# HDMI.net
KiCad netlist of a schematic drawn in Altium Designer
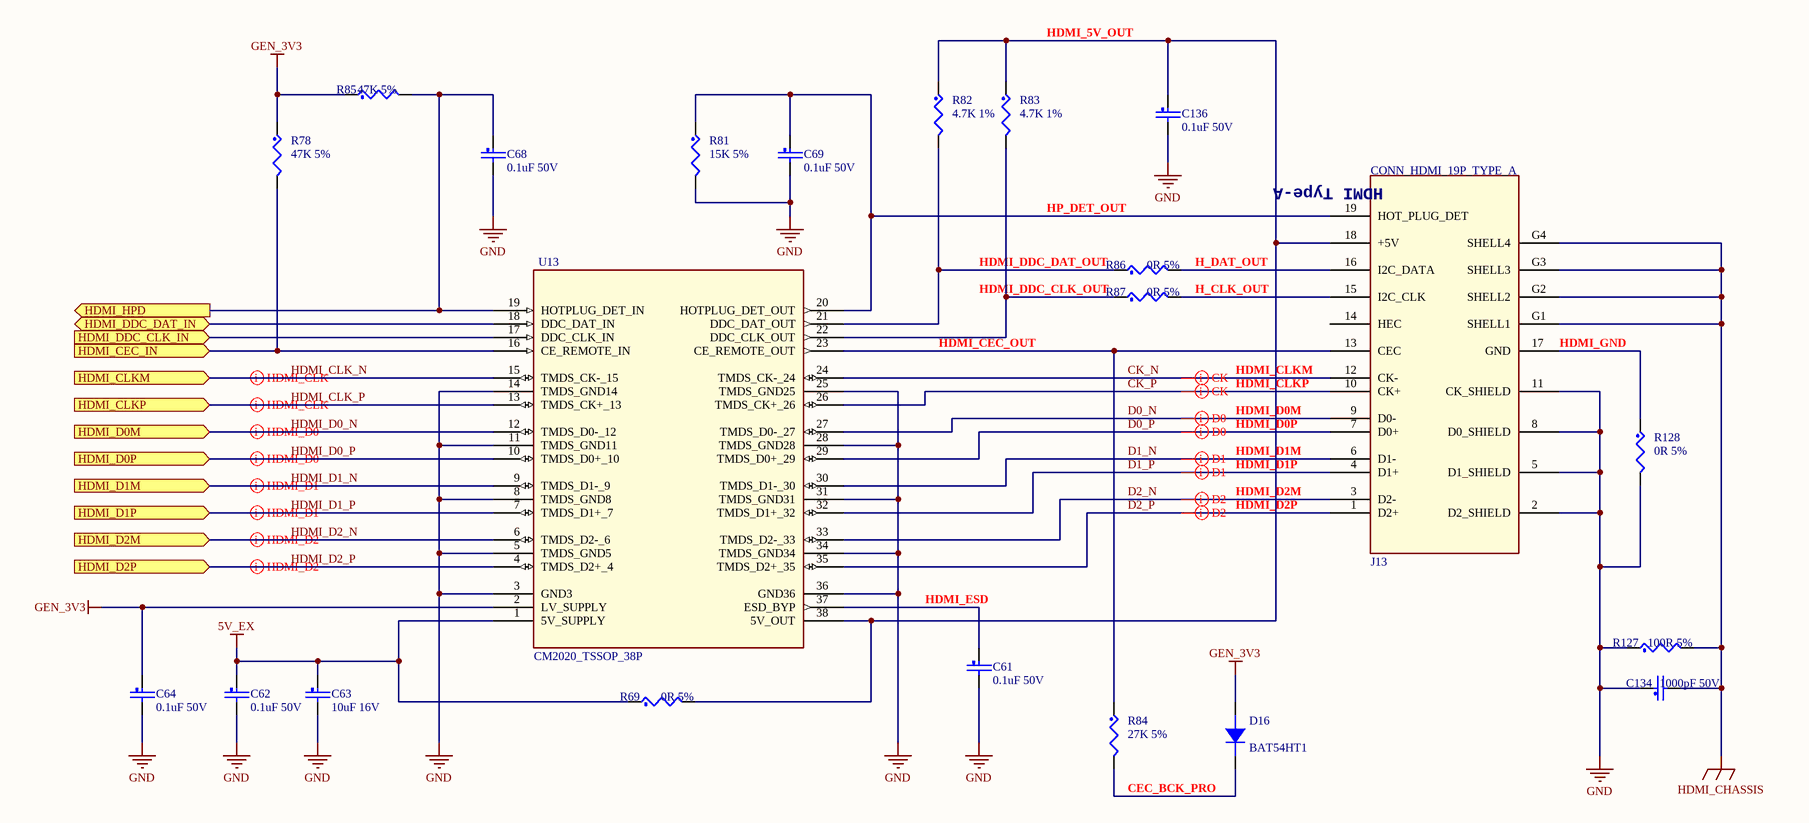
[diagram p0: HDMI.SchDoc]

(export (version "E")
  (design (tool "Eeschema 10.0.6"))
  (components
    (comp (ref "C61")
      (value "0.1uF 50V")
      (footprint "SC0603")
      (libsource (lib "MY-I.MX6-SCH_Library") (part "CAP_NP"))
    )
    (comp (ref "C62")
      (value "0.1uF 50V")
      (footprint "SC0603")
      (libsource (lib "MY-I.MX6-SCH_Library") (part "CAP_NP"))
    )
    (comp (ref "C63")
      (value "10uF 16V")
      (footprint "SC0805")
      (libsource (lib "MY-I.MX6-SCH_Library") (part "CAP_NP"))
    )
    (comp (ref "C64")
      (value "0.1uF 50V")
      (footprint "SC0603")
      (libsource (lib "MY-I.MX6-SCH_Library") (part "CAP_NP"))
    )
    (comp (ref "C68")
      (value "0.1uF 50V")
      (footprint "SC0603")
      (libsource (lib "MY-I.MX6-SCH_Library") (part "CAP_NP"))
    )
    (comp (ref "C69")
      (value "0.1uF 50V")
      (footprint "SC0603")
      (libsource (lib "MY-I.MX6-SCH_Library") (part "CAP_NP"))
    )
    (comp (ref "C134")
      (value "1000pF 50V")
      (footprint "SC0603")
      (libsource (lib "MY-I.MX6-SCH_Library") (part "CAP_NP"))
    )
    (comp (ref "C136")
      (value "0.1uF 50V")
      (footprint "SC0603")
      (libsource (lib "MY-I.MX6-SCH_Library") (part "CAP_NP"))
    )
    (comp (ref "D16")
      (value "BAT54HT1")
      (footprint "SOD323")
      (libsource (lib "MY-I.MX6-SCH_Library") (part "DIODE_0"))
    )
    (comp (ref "J13")
      (value "CONN_HDMI_19P_TYPE_A")
      (footprint "HDMI-A-LIANSHENG")
      (libsource (lib "MY-I.MX6-SCH_Library") (part "CONN_HDMI_19P_TYPE_A"))
    )
    (comp (ref "R69")
      (value "0R 5%")
      (footprint "SR0603")
      (libsource (lib "MY-I.MX6-SCH_Library") (part "RES"))
    )
    (comp (ref "R78")
      (value "47K 5%")
      (footprint "SR0603")
      (libsource (lib "MY-I.MX6-SCH_Library") (part "RES"))
    )
    (comp (ref "R81")
      (value "15K 5%")
      (footprint "SR0603")
      (libsource (lib "MY-I.MX6-SCH_Library") (part "RES"))
    )
    (comp (ref "R82")
      (value "4.7K 1%")
      (footprint "SR0603")
      (libsource (lib "MY-I.MX6-SCH_Library") (part "RES"))
    )
    (comp (ref "R83")
      (value "4.7K 1%")
      (footprint "SR0603")
      (libsource (lib "MY-I.MX6-SCH_Library") (part "RES"))
    )
    (comp (ref "R84")
      (value "27K 5%")
      (footprint "SR0603")
      (libsource (lib "MY-I.MX6-SCH_Library") (part "RES"))
    )
    (comp (ref "R85")
      (value "47K 5%")
      (footprint "SR0603")
      (libsource (lib "MY-I.MX6-SCH_Library") (part "RES"))
    )
    (comp (ref "R86")
      (value "0R 5%")
      (footprint "SR0603")
      (libsource (lib "MY-I.MX6-SCH_Library") (part "RES"))
    )
    (comp (ref "R87")
      (value "0R 5%")
      (footprint "SR0603")
      (libsource (lib "MY-I.MX6-SCH_Library") (part "RES"))
    )
    (comp (ref "R127")
      (value "100R 5%")
      (footprint "SR0603")
      (libsource (lib "MY-I.MX6-SCH_Library") (part "RES"))
    )
    (comp (ref "R128")
      (value "0R 5%")
      (footprint "SR0603")
      (libsource (lib "MY-I.MX6-SCH_Library") (part "RES"))
    )
    (comp (ref "U13")
      (value "CM2020_TSSOP_38P")
      (footprint "TSSOP38-0P5-9P8X4P5")
      (libsource (lib "MY-I.MX6-SCH_Library") (part "CM2020_TSSOP_38P"))
    )
  )
  (nets
    (net (code "1") (name "/CK_N") (class "Default")
      (node (ref "J13") (pin "12") (pinfunction "CK-_12") (pintype "passive"))
      (node (ref "U13") (pin "24") (pinfunction "TMDS_CK-_24_24") (pintype "bidirectional"))
    )
    (net (code "2") (name "/CK_P") (class "Default")
      (node (ref "J13") (pin "10") (pinfunction "CK+_10") (pintype "passive"))
      (node (ref "U13") (pin "26") (pinfunction "TMDS_CK+_26_26") (pintype "bidirectional"))
    )
    (net (code "3") (name "/D0_N") (class "Default")
      (node (ref "J13") (pin "9") (pinfunction "D0-_9") (pintype "passive"))
      (node (ref "U13") (pin "27") (pinfunction "TMDS_D0-_27_27") (pintype "bidirectional"))
    )
    (net (code "4") (name "/D0_P") (class "Default")
      (node (ref "J13") (pin "7") (pinfunction "D0+_7") (pintype "passive"))
      (node (ref "U13") (pin "29") (pinfunction "TMDS_D0+_29_29") (pintype "bidirectional"))
    )
    (net (code "5") (name "/D1_N") (class "Default")
      (node (ref "J13") (pin "6") (pinfunction "D1-_6") (pintype "passive"))
      (node (ref "U13") (pin "30") (pinfunction "TMDS_D1-_30_30") (pintype "bidirectional"))
    )
    (net (code "6") (name "/D1_P") (class "Default")
      (node (ref "J13") (pin "4") (pinfunction "D1+_4") (pintype "passive"))
      (node (ref "U13") (pin "32") (pinfunction "TMDS_D1+_32_32") (pintype "bidirectional"))
    )
    (net (code "7") (name "/D2_N") (class "Default")
      (node (ref "J13") (pin "3") (pinfunction "D2-_3") (pintype "passive"))
      (node (ref "U13") (pin "33") (pinfunction "TMDS_D2-_33_33") (pintype "bidirectional"))
    )
    (net (code "8") (name "/D2_P") (class "Default")
      (node (ref "J13") (pin "1") (pinfunction "D2+_1") (pintype "passive"))
      (node (ref "U13") (pin "35") (pinfunction "TMDS_D2+_35_35") (pintype "bidirectional"))
    )
    (net (code "9") (name "/HDMI_CEC_IN") (class "Default")
      (node (ref "R78") (pin "2") (pinfunction "2_2") (pintype "passive"))
      (node (ref "U13") (pin "16") (pinfunction "CE_REMOTE_IN_16") (pintype "input"))
    )
    (net (code "10") (name "/HDMI_CLK_N") (class "Default")
      (node (ref "U13") (pin "15") (pinfunction "TMDS_CK-_15_15") (pintype "bidirectional"))
    )
    (net (code "11") (name "/HDMI_CLK_P") (class "Default")
      (node (ref "U13") (pin "13") (pinfunction "TMDS_CK+_13_13") (pintype "bidirectional"))
    )
    (net (code "12") (name "/HDMI_D0_N") (class "Default")
      (node (ref "U13") (pin "12") (pinfunction "TMDS_D0-_12_12") (pintype "bidirectional"))
    )
    (net (code "13") (name "/HDMI_D0_P") (class "Default")
      (node (ref "U13") (pin "10") (pinfunction "TMDS_D0+_10_10") (pintype "bidirectional"))
    )
    (net (code "14") (name "/HDMI_D1_N") (class "Default")
      (node (ref "U13") (pin "9") (pinfunction "TMDS_D1-_9_9") (pintype "bidirectional"))
    )
    (net (code "15") (name "/HDMI_D1_P") (class "Default")
      (node (ref "U13") (pin "7") (pinfunction "TMDS_D1+_7_7") (pintype "bidirectional"))
    )
    (net (code "16") (name "/HDMI_D2_N") (class "Default")
      (node (ref "U13") (pin "6") (pinfunction "TMDS_D2-_6_6") (pintype "bidirectional"))
    )
    (net (code "17") (name "/HDMI_D2_P") (class "Default")
      (node (ref "U13") (pin "4") (pinfunction "TMDS_D2+_4_4") (pintype "bidirectional"))
    )
    (net (code "18") (name "/HDMI_DDC_CLK_IN") (class "Default")
      (node (ref "U13") (pin "17") (pinfunction "DDC_CLK_IN_17") (pintype "input"))
    )
    (net (code "19") (name "/HDMI_DDC_DAT_IN") (class "Default")
      (node (ref "U13") (pin "18") (pinfunction "DDC_DAT_IN_18") (pintype "input"))
    )
    (net (code "20") (name "/HDMI_HPD") (class "Default")
      (node (ref "C68") (pin "1") (pinfunction "1_1") (pintype "passive"))
      (node (ref "R85") (pin "2") (pinfunction "2_2") (pintype "passive"))
      (node (ref "U13") (pin "19") (pinfunction "HOTPLUG_DET_IN_19") (pintype "input"))
    )
    (net (code "21") (name "5V_EX") (class "Default")
      (node (ref "C62") (pin "1") (pinfunction "1_1") (pintype "passive"))
      (node (ref "C63") (pin "1") (pinfunction "1_1") (pintype "passive"))
      (node (ref "R69") (pin "1") (pinfunction "1_1") (pintype "passive"))
      (node (ref "U13") (pin "1") (pinfunction "5V_SUPPLY_1") (pintype "power_in"))
    )
    (net (code "22") (name "GEN_3V3") (class "Default")
      (node (ref "C64") (pin "1") (pinfunction "1_1") (pintype "passive"))
      (node (ref "D16") (pin "1") (pinfunction "1_1") (pintype "passive"))
      (node (ref "R78") (pin "1") (pinfunction "1_1") (pintype "passive"))
      (node (ref "R85") (pin "1") (pinfunction "1_1") (pintype "passive"))
      (node (ref "U13") (pin "2") (pinfunction "LV_SUPPLY_2") (pintype "power_in"))
    )
    (net (code "23") (name "GND") (class "Default")
      (node (ref "C134") (pin "1") (pinfunction "1_1") (pintype "passive"))
      (node (ref "C136") (pin "2") (pinfunction "2_2") (pintype "passive"))
      (node (ref "C61") (pin "2") (pinfunction "2_2") (pintype "passive"))
      (node (ref "C62") (pin "2") (pinfunction "2_2") (pintype "passive"))
      (node (ref "C63") (pin "2") (pinfunction "2_2") (pintype "passive"))
      (node (ref "C64") (pin "2") (pinfunction "2_2") (pintype "passive"))
      (node (ref "C68") (pin "2") (pinfunction "2_2") (pintype "passive"))
      (node (ref "C69") (pin "2") (pinfunction "2_2") (pintype "passive"))
      (node (ref "J13") (pin "11") (pinfunction "CK_SHIELD_11") (pintype "passive"))
      (node (ref "J13") (pin "2") (pinfunction "D2_SHIELD_2") (pintype "passive"))
      (node (ref "J13") (pin "5") (pinfunction "D1_SHIELD_5") (pintype "passive"))
      (node (ref "J13") (pin "8") (pinfunction "D0_SHIELD_8") (pintype "passive"))
      (node (ref "R127") (pin "1") (pinfunction "1_1") (pintype "passive"))
      (node (ref "R128") (pin "2") (pinfunction "2_2") (pintype "passive"))
      (node (ref "R81") (pin "2") (pinfunction "2_2") (pintype "passive"))
      (node (ref "U13") (pin "11") (pinfunction "TMDS_GND11_11") (pintype "power_in"))
      (node (ref "U13") (pin "14") (pinfunction "TMDS_GND14_14") (pintype "power_in"))
      (node (ref "U13") (pin "25") (pinfunction "TMDS_GND25_25") (pintype "power_in"))
      (node (ref "U13") (pin "28") (pinfunction "TMDS_GND28_28") (pintype "power_in"))
      (node (ref "U13") (pin "3") (pinfunction "GND3_3") (pintype "power_in"))
      (node (ref "U13") (pin "31") (pinfunction "TMDS_GND31_31") (pintype "power_in"))
      (node (ref "U13") (pin "34") (pinfunction "TMDS_GND34_34") (pintype "power_in"))
      (node (ref "U13") (pin "36") (pinfunction "GND36_36") (pintype "power_in"))
      (node (ref "U13") (pin "5") (pinfunction "TMDS_GND5_5") (pintype "power_in"))
      (node (ref "U13") (pin "8") (pinfunction "TMDS_GND8_8") (pintype "power_in"))
    )
    (net (code "24") (name "HDMI_CHASSIS") (class "Default")
      (node (ref "C134") (pin "2") (pinfunction "2_2") (pintype "passive"))
      (node (ref "J13") (pin "G1") (pinfunction "SHELL1_G1") (pintype "passive"))
      (node (ref "J13") (pin "G2") (pinfunction "SHELL2_G2") (pintype "passive"))
      (node (ref "J13") (pin "G3") (pinfunction "SHELL3_G3") (pintype "passive"))
      (node (ref "J13") (pin "G4") (pinfunction "SHELL4_G4") (pintype "passive"))
      (node (ref "R127") (pin "2") (pinfunction "2_2") (pintype "passive"))
    )
    (net (code "25") (name "Net-(D16-Pad2)") (class "Default")
      (node (ref "D16") (pin "2") (pinfunction "2_2") (pintype "passive"))
      (node (ref "R84") (pin "2") (pinfunction "2_2") (pintype "passive"))
    )
    (net (code "26") (name "Net-(J13-+5V)") (class "Default")
      (node (ref "C136") (pin "1") (pinfunction "1_1") (pintype "passive"))
      (node (ref "J13") (pin "18") (pinfunction "+5V_18") (pintype "passive"))
      (node (ref "R69") (pin "2") (pinfunction "2_2") (pintype "passive"))
      (node (ref "R82") (pin "1") (pinfunction "1_1") (pintype "passive"))
      (node (ref "R83") (pin "1") (pinfunction "1_1") (pintype "passive"))
      (node (ref "U13") (pin "38") (pinfunction "5V_OUT_38") (pintype "power_in"))
    )
    (net (code "27") (name "Net-(J13-CEC)") (class "Default")
      (node (ref "J13") (pin "13") (pinfunction "CEC_13") (pintype "passive"))
      (node (ref "R84") (pin "1") (pinfunction "1_1") (pintype "passive"))
      (node (ref "U13") (pin "23") (pinfunction "CE_REMOTE_OUT_23") (pintype "output"))
    )
    (net (code "28") (name "Net-(J13-GND)") (class "Default")
      (node (ref "J13") (pin "17") (pinfunction "GND_17") (pintype "passive"))
      (node (ref "R128") (pin "1") (pinfunction "1_1") (pintype "passive"))
    )
    (net (code "29") (name "Net-(J13-HOT_PLUG_DET)") (class "Default")
      (node (ref "C69") (pin "1") (pinfunction "1_1") (pintype "passive"))
      (node (ref "J13") (pin "19") (pinfunction "HOT_PLUG_DET_19") (pintype "passive"))
      (node (ref "R81") (pin "1") (pinfunction "1_1") (pintype "passive"))
      (node (ref "U13") (pin "20") (pinfunction "HOTPLUG_DET_OUT_20") (pintype "output"))
    )
    (net (code "30") (name "Net-(J13-I2C_CLK)") (class "Default")
      (node (ref "J13") (pin "15") (pinfunction "I2C_CLK_15") (pintype "passive"))
      (node (ref "R87") (pin "2") (pinfunction "2_2") (pintype "passive"))
    )
    (net (code "31") (name "Net-(J13-I2C_DATA)") (class "Default")
      (node (ref "J13") (pin "16") (pinfunction "I2C_DATA_16") (pintype "passive"))
      (node (ref "R86") (pin "2") (pinfunction "2_2") (pintype "passive"))
    )
    (net (code "32") (name "Net-(U13-DDC_CLK_OUT)") (class "Default")
      (node (ref "R83") (pin "2") (pinfunction "2_2") (pintype "passive"))
      (node (ref "R87") (pin "1") (pinfunction "1_1") (pintype "passive"))
      (node (ref "U13") (pin "22") (pinfunction "DDC_CLK_OUT_22") (pintype "output"))
    )
    (net (code "33") (name "Net-(U13-DDC_DAT_OUT)") (class "Default")
      (node (ref "R82") (pin "2") (pinfunction "2_2") (pintype "passive"))
      (node (ref "R86") (pin "1") (pinfunction "1_1") (pintype "passive"))
      (node (ref "U13") (pin "21") (pinfunction "DDC_DAT_OUT_21") (pintype "output"))
    )
    (net (code "34") (name "Net-(U13-ESD_BYP)") (class "Default")
      (node (ref "C61") (pin "1") (pinfunction "1_1") (pintype "passive"))
      (node (ref "U13") (pin "37") (pinfunction "ESD_BYP_37") (pintype "output"))
    )
    (net (code "35") (name "unconnected-(J13-HEC-Pad14)") (class "Default")
      (node (ref "J13") (pin "14") (pinfunction "HEC_14") (pintype "passive"))
    )
  )
)
